# CH32V203K8T6-R0.net
KiCad netlist of a schematic drawn in Altium Designer
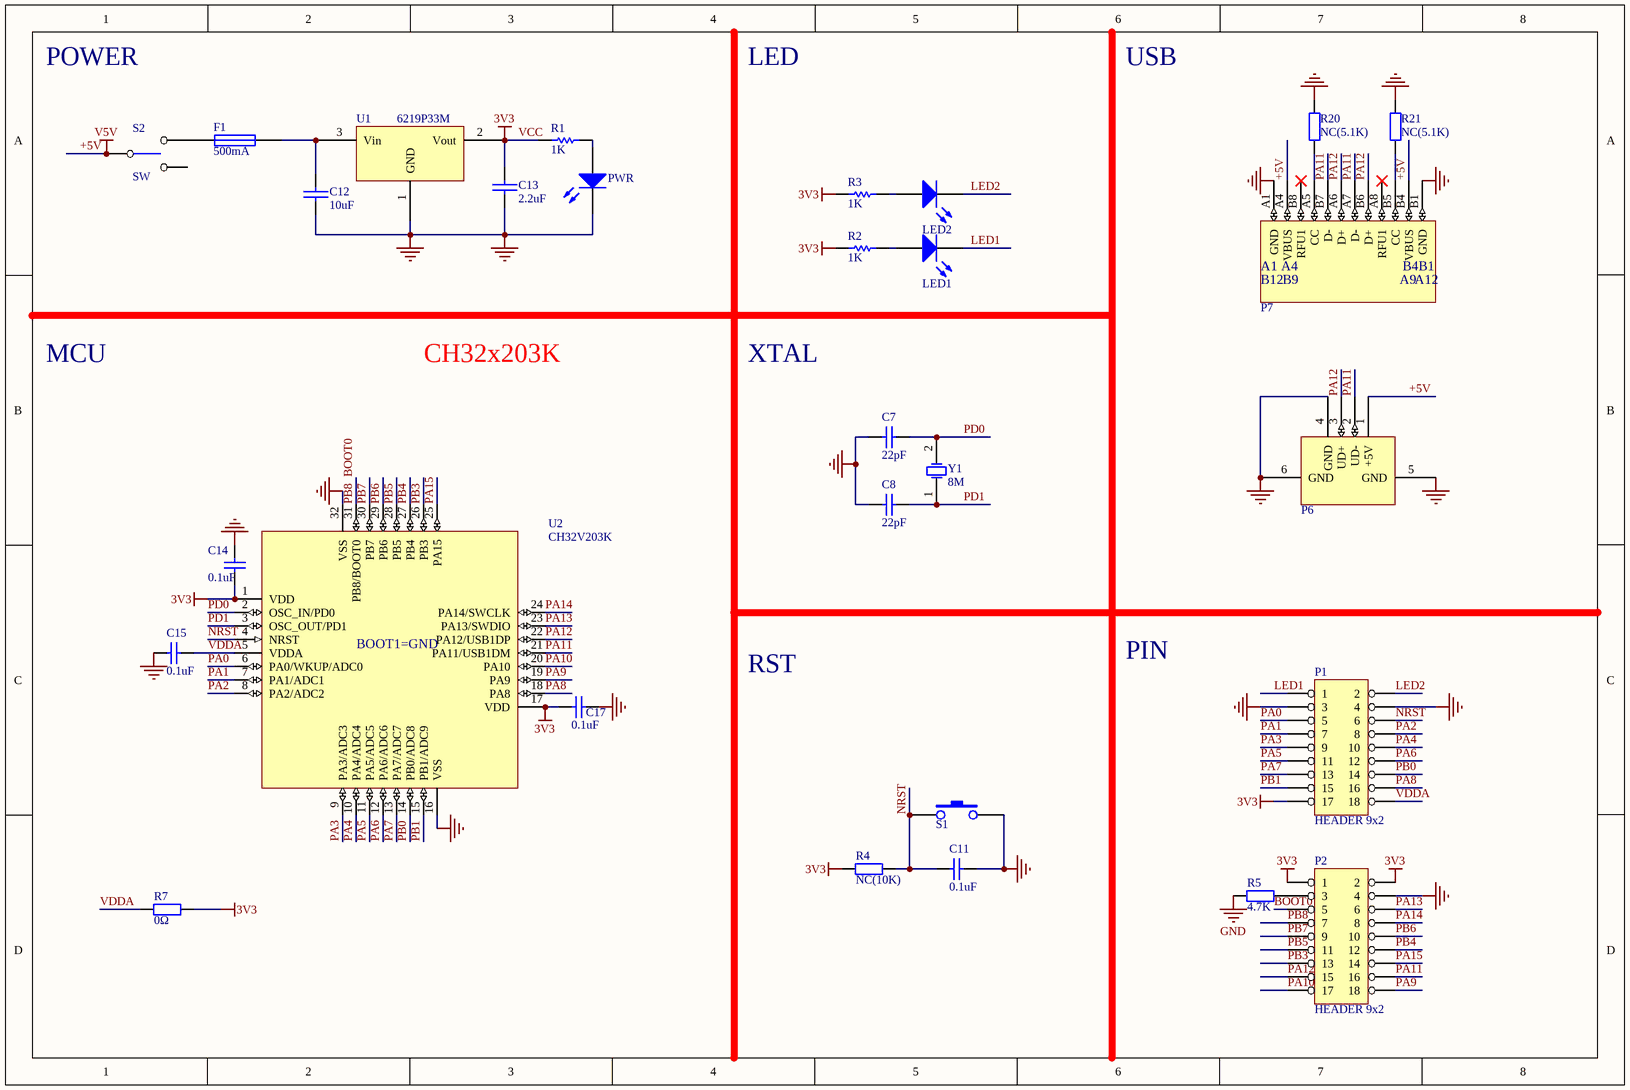
[diagram p0: CH32V203K8T6-R0.SchDoc]

(export (version "E")
  (design (tool "Eeschema 10.0.6"))
  (components
    (comp (ref "C7")
      (value "22pF")
      (footprint "0603_C")
      (description "Capacitor")
      (fields (field (name "PUBLISHER") "Altium Limited"))
      (libsource (lib "*") (part "Cap"))
    )
    (comp (ref "C8")
      (value "22pF")
      (footprint "0603_C")
      (description "Capacitor")
      (fields (field (name "PUBLISHER") "Altium Limited"))
      (libsource (lib "*") (part "Cap"))
    )
    (comp (ref "C11")
      (value "0.1uF")
      (footprint "0603_C")
      (description "Capacitor")
      (fields (field (name "PUBLISHER") "Altium Limited"))
      (libsource (lib "*") (part "Cap"))
    )
    (comp (ref "C12")
      (value "10uF")
      (footprint "3216_C")
      (description "Capacitor")
      (libsource (lib "wch_sch_others") (part "CAP"))
    )
    (comp (ref "C13")
      (value "2.2uF")
      (footprint "0603_C")
      (description "Capacitor")
      (libsource (lib "wch_sch_others") (part "CAP"))
    )
    (comp (ref "C14")
      (value "0.1uF")
      (footprint "0603_C")
      (description "Capacitor")
      (fields (field (name "PUBLISHER") "Altium Limited"))
      (libsource (lib "*") (part "Cap"))
    )
    (comp (ref "C15")
      (value "0.1uF")
      (footprint "0603_C")
      (description "Capacitor")
      (fields (field (name "PUBLISHER") "Altium Limited"))
      (libsource (lib "*") (part "Cap"))
    )
    (comp (ref "C17")
      (value "0.1uF")
      (footprint "0603_C")
      (description "Capacitor")
      (fields (field (name "PUBLISHER") "Altium Limited"))
      (libsource (lib "*") (part "Cap"))
    )
    (comp (ref "F1")
      (value "500mA")
      (footprint "0603")
      (description "Fuse")
      (libsource (lib "*") (part "FUSE1"))
    )
    (comp (ref "LED1")
      (value "LED1   blue")
      (footprint "0603+")
      (description "Typical INFRARED GaAs LED")
      (fields (field (name "PUBLISHER") "Altium Limited"))
      (libsource (lib "*") (part "LED0"))
    )
    (comp (ref "LED2")
      (value "LED2  blue")
      (footprint "0603+")
      (description "Typical INFRARED GaAs LED")
      (fields (field (name "PUBLISHER") "Altium Limited"))
      (libsource (lib "*") (part "LED0"))
    )
    (comp (ref "P1")
      (value "HEADER 9x2")
      (footprint "MYPCB:IDC18-2.54MM")
      (description "Header, 9-Pin, Dual row")
      (libsource (lib "wch_sch_others") (part "HEADER 9x2"))
    )
    (comp (ref "P2")
      (value "HEADER 9x2")
      (footprint "MYPCB:IDC18-2.54MM")
      (description "Header, 9-Pin, Dual row")
      (libsource (lib "wch_sch_others") (part "HEADER 9x2"))
    )
    (comp (ref "P6")
      (value "USB_A")
      (footprint "USBAF")
      (description "USB Port")
      (libsource (lib "*") (part "USB"))
    )
    (comp (ref "P7")
      (value "TYPE-C")
      (footprint "TYPE-C-Receptacle-2.0")
      (libsource (lib "*") (part "TYPE-C1"))
    )
    (comp (ref "PWR")
      (value "POWER  red")
      (footprint "0603+")
      (description "Typical INFRARED GaAs LED")
      (fields (field (name "PUBLISHER") "Altium Limited"))
      (libsource (lib "*") (part "LED0"))
    )
    (comp (ref "R1")
      (value "1K")
      (footprint "0603")
      (description "Semiconductor Resistor")
      (fields (field (name "PUBLISHER") "Altium Limited"))
      (libsource (lib "*") (part "Res Semi"))
    )
    (comp (ref "R2")
      (value "1K")
      (footprint "0603")
      (description "Semiconductor Resistor")
      (fields (field (name "PUBLISHER") "Altium Limited"))
      (libsource (lib "*") (part "Res Semi"))
    )
    (comp (ref "R3")
      (value "1K")
      (footprint "0603")
      (description "Semiconductor Resistor")
      (fields (field (name "PUBLISHER") "Altium Limited"))
      (libsource (lib "*") (part "Res Semi"))
    )
    (comp (ref "R4")
      (value "NC(10K)")
      (footprint "0603")
      (description "Resistor")
      (fields (field (name "PUBLISHER") "Altium Limited"))
      (libsource (lib "*") (part "Res2"))
    )
    (comp (ref "R5")
      (value "4.7K")
      (footprint "0603")
      (description "Resistor")
      (fields (field (name "PUBLISHER") "Altium Limited"))
      (libsource (lib "") (part "Res2_1"))
    )
    (comp (ref "R7")
      (value "0Ω")
      (footprint "0603")
      (description "Resistor")
      (fields (field (name "PUBLISHER") "Altium Limited"))
      (libsource (lib "*") (part "Res2"))
    )
    (comp (ref "R20")
      (value "NC(5.1K)")
      (footprint "0603")
      (description "Resistor")
      (libsource (lib "Miscellaneous Devices") (part "Res2"))
    )
    (comp (ref "R21")
      (value "NC(5.1K)")
      (footprint "0603")
      (description "Resistor")
      (libsource (lib "Miscellaneous Devices") (part "Res2"))
    )
    (comp (ref "S1") (value "RST") (footprint "SMD_6.1x3.65x2.5mm-KEY") (libsource (lib "*") (part "KEY")))
    (comp (ref "S2") (value "SW") (footprint "KEY2") (libsource (lib "*") (part "SW")))
    (comp (ref "U1")
      (value "6219P33M")
      (footprint "SOT-23")
      (libsource (lib "wch_sch_others") (part "6219P33M"))
    )
    (comp (ref "U2")
      (value "CH32V203K")
      (footprint "LQFP32")
      (description "RISC-V LMD-MCU, 144MHz, USB FS, CAN")
      (libsource (lib "CHXXX") (part "CH32V203K"))
    )
    (comp (ref "Y1")
      (value "8M")
      (footprint "XT_AT49")
      (description "Crystal Oscillator")
      (fields (field (name "PUBLISHER") "Altium Limited"))
      (libsource (lib "*") (part "XTAL"))
    )
  )
  (nets
    (net (code "2") (name "/BOOT0") (class "Default")
      (node (ref "P2") (pin "5") (pinfunction "5_5") (pintype "passive"))
      (node (ref "P2") (pin "7") (pinfunction "7_7") (pintype "passive"))
      (node (ref "U2") (pin "31") (pinfunction "PB8/BOOT0_31") (pintype "bidirectional"))
    )
    (net (code "3") (name "/LED1") (class "Default")
      (node (ref "LED1") (pin "2") (pinfunction "K_2") (pintype "passive"))
      (node (ref "P1") (pin "1") (pinfunction "1_1") (pintype "passive"))
    )
    (net (code "4") (name "/LED2") (class "Default")
      (node (ref "LED2") (pin "2") (pinfunction "K_2") (pintype "passive"))
      (node (ref "P1") (pin "2") (pinfunction "2_2") (pintype "passive"))
    )
    (net (code "5") (name "/NRST") (class "Default")
      (node (ref "C11") (pin "2") (pinfunction "2_2") (pintype "passive"))
      (node (ref "P1") (pin "6") (pinfunction "6_6") (pintype "passive"))
      (node (ref "R4") (pin "1") (pinfunction "1_1") (pintype "passive"))
      (node (ref "S1") (pin "1") (pinfunction "1_1") (pintype "passive"))
      (node (ref "U2") (pin "4") (pinfunction "NRST_4") (pintype "input"))
    )
    (net (code "6") (name "/PA0") (class "Default")
      (node (ref "P1") (pin "5") (pinfunction "5_5") (pintype "passive"))
      (node (ref "U2") (pin "6") (pinfunction "PA0/WKUP/ADC0_6") (pintype "bidirectional"))
    )
    (net (code "7") (name "/PA1") (class "Default")
      (node (ref "P1") (pin "7") (pinfunction "7_7") (pintype "passive"))
      (node (ref "U2") (pin "7") (pinfunction "PA1/ADC1_7") (pintype "bidirectional"))
    )
    (net (code "8") (name "/PA2") (class "Default")
      (node (ref "P1") (pin "8") (pinfunction "8_8") (pintype "passive"))
      (node (ref "U2") (pin "8") (pinfunction "PA2/ADC2_8") (pintype "bidirectional"))
    )
    (net (code "9") (name "/PA3") (class "Default")
      (node (ref "P1") (pin "9") (pinfunction "9_9") (pintype "passive"))
      (node (ref "U2") (pin "9") (pinfunction "PA3/ADC3_9") (pintype "bidirectional"))
    )
    (net (code "10") (name "/PA4") (class "Default")
      (node (ref "P1") (pin "10") (pinfunction "10_10") (pintype "passive"))
      (node (ref "U2") (pin "10") (pinfunction "PA4/ADC4_10") (pintype "bidirectional"))
    )
    (net (code "11") (name "/PA5") (class "Default")
      (node (ref "P1") (pin "11") (pinfunction "11_11") (pintype "passive"))
      (node (ref "U2") (pin "11") (pinfunction "PA5/ADC5_11") (pintype "bidirectional"))
    )
    (net (code "12") (name "/PA6") (class "Default")
      (node (ref "P1") (pin "12") (pinfunction "12_12") (pintype "passive"))
      (node (ref "U2") (pin "12") (pinfunction "PA6/ADC6_12") (pintype "bidirectional"))
    )
    (net (code "13") (name "/PA7") (class "Default")
      (node (ref "P1") (pin "13") (pinfunction "13_13") (pintype "passive"))
      (node (ref "U2") (pin "13") (pinfunction "PA7/ADC7_13") (pintype "bidirectional"))
    )
    (net (code "14") (name "/PA8") (class "Default")
      (node (ref "P1") (pin "16") (pinfunction "16_16") (pintype "passive"))
      (node (ref "U2") (pin "18") (pinfunction "PA8_18") (pintype "bidirectional"))
    )
    (net (code "15") (name "/PA9") (class "Default")
      (node (ref "P2") (pin "18") (pinfunction "18_18") (pintype "passive"))
      (node (ref "U2") (pin "19") (pinfunction "PA9_19") (pintype "bidirectional"))
    )
    (net (code "16") (name "/PA10") (class "Default")
      (node (ref "P2") (pin "17") (pinfunction "17_17") (pintype "passive"))
      (node (ref "U2") (pin "20") (pinfunction "PA10_20") (pintype "bidirectional"))
    )
    (net (code "17") (name "/PA11") (class "Default")
      (node (ref "P2") (pin "16") (pinfunction "16_16") (pintype "passive"))
      (node (ref "P6") (pin "2") (pinfunction "UD-_2") (pintype "bidirectional"))
      (node (ref "P7") (pin "A7") (pinfunction "D-_A7") (pintype "bidirectional"))
      (node (ref "P7") (pin "B7") (pinfunction "D-_B7") (pintype "bidirectional"))
      (node (ref "U2") (pin "21") (pinfunction "PA11/USB1DM_21") (pintype "bidirectional"))
    )
    (net (code "18") (name "/PA12") (class "Default")
      (node (ref "P2") (pin "15") (pinfunction "15_15") (pintype "passive"))
      (node (ref "P6") (pin "3") (pinfunction "UD+_3") (pintype "bidirectional"))
      (node (ref "P7") (pin "A6") (pinfunction "D+_A6") (pintype "bidirectional"))
      (node (ref "P7") (pin "B6") (pinfunction "D+_B6") (pintype "bidirectional"))
      (node (ref "U2") (pin "22") (pinfunction "PA12/USB1DP_22") (pintype "bidirectional"))
    )
    (net (code "19") (name "/PA13") (class "Default")
      (node (ref "P2") (pin "6") (pinfunction "6_6") (pintype "passive"))
      (node (ref "U2") (pin "23") (pinfunction "PA13/SWDIO_23") (pintype "bidirectional"))
    )
    (net (code "20") (name "/PA14") (class "Default")
      (node (ref "P2") (pin "8") (pinfunction "8_8") (pintype "passive"))
      (node (ref "U2") (pin "24") (pinfunction "PA14/SWCLK_24") (pintype "bidirectional"))
    )
    (net (code "21") (name "/PA15") (class "Default")
      (node (ref "P2") (pin "14") (pinfunction "14_14") (pintype "passive"))
      (node (ref "U2") (pin "25") (pinfunction "PA15_25") (pintype "bidirectional"))
    )
    (net (code "22") (name "/PB0") (class "Default")
      (node (ref "P1") (pin "14") (pinfunction "14_14") (pintype "passive"))
      (node (ref "U2") (pin "14") (pinfunction "PB0/ADC8_14") (pintype "bidirectional"))
    )
    (net (code "23") (name "/PB1") (class "Default")
      (node (ref "P1") (pin "15") (pinfunction "15_15") (pintype "passive"))
      (node (ref "U2") (pin "15") (pinfunction "PB1/ADC9_15") (pintype "bidirectional"))
    )
    (net (code "24") (name "/PB3") (class "Default")
      (node (ref "P2") (pin "13") (pinfunction "13_13") (pintype "passive"))
      (node (ref "U2") (pin "26") (pinfunction "PB3_26") (pintype "bidirectional"))
    )
    (net (code "25") (name "/PB4") (class "Default")
      (node (ref "P2") (pin "12") (pinfunction "12_12") (pintype "passive"))
      (node (ref "U2") (pin "27") (pinfunction "PB4_27") (pintype "bidirectional"))
    )
    (net (code "26") (name "/PB5") (class "Default")
      (node (ref "P2") (pin "11") (pinfunction "11_11") (pintype "passive"))
      (node (ref "U2") (pin "28") (pinfunction "PB5_28") (pintype "bidirectional"))
    )
    (net (code "27") (name "/PB6") (class "Default")
      (node (ref "P2") (pin "10") (pinfunction "10_10") (pintype "passive"))
      (node (ref "U2") (pin "29") (pinfunction "PB6_29") (pintype "bidirectional"))
    )
    (net (code "28") (name "/PB7") (class "Default")
      (node (ref "P2") (pin "9") (pinfunction "9_9") (pintype "passive"))
      (node (ref "U2") (pin "30") (pinfunction "PB7_30") (pintype "bidirectional"))
    )
    (net (code "29") (name "/PD0") (class "Default")
      (node (ref "C7") (pin "2") (pinfunction "2_2") (pintype "passive"))
      (node (ref "U2") (pin "2") (pinfunction "OSC_IN/PD0_2") (pintype "bidirectional"))
      (node (ref "Y1") (pin "2") (pinfunction "OSC2_2") (pintype "passive"))
    )
    (net (code "30") (name "/PD1") (class "Default")
      (node (ref "C8") (pin "2") (pinfunction "2_2") (pintype "passive"))
      (node (ref "U2") (pin "3") (pinfunction "OSC_OUT/PD1_3") (pintype "bidirectional"))
      (node (ref "Y1") (pin "1") (pinfunction "OSC1_1") (pintype "passive"))
    )
    (net (code "31") (name "/VDDA") (class "Default")
      (node (ref "C15") (pin "1") (pinfunction "1_1") (pintype "passive"))
      (node (ref "P1") (pin "18") (pinfunction "18_18") (pintype "passive"))
      (node (ref "R7") (pin "2") (pinfunction "2_2") (pintype "passive"))
      (node (ref "U2") (pin "5") (pinfunction "VDDA_5") (pintype "power_in"))
    )
    (net (code "32") (name "3V3") (class "Default")
      (node (ref "C13") (pin "2") (pinfunction "2_2") (pintype "passive"))
      (node (ref "C14") (pin "2") (pinfunction "2_2") (pintype "passive"))
      (node (ref "C17") (pin "1") (pinfunction "1_1") (pintype "passive"))
      (node (ref "P1") (pin "17") (pinfunction "17_17") (pintype "passive"))
      (node (ref "P2") (pin "1") (pinfunction "1_1") (pintype "passive"))
      (node (ref "P2") (pin "2") (pinfunction "2_2") (pintype "passive"))
      (node (ref "R1") (pin "2") (pinfunction "2_2") (pintype "passive"))
      (node (ref "R2") (pin "1") (pinfunction "1_1") (pintype "passive"))
      (node (ref "R3") (pin "1") (pinfunction "1_1") (pintype "passive"))
      (node (ref "R4") (pin "2") (pinfunction "2_2") (pintype "passive"))
      (node (ref "R7") (pin "1") (pinfunction "1_1") (pintype "passive"))
      (node (ref "U1") (pin "2") (pinfunction "Vout_2") (pintype "passive"))
      (node (ref "U2") (pin "1") (pinfunction "VDD_1") (pintype "power_in"))
      (node (ref "U2") (pin "17") (pinfunction "VDD_17") (pintype "power_in"))
    )
    (net (code "33") (name "GND") (class "Default")
      (node (ref "C11") (pin "1") (pinfunction "1_1") (pintype "passive"))
      (node (ref "C12") (pin "2") (pinfunction "2_2") (pintype "passive"))
      (node (ref "C13") (pin "1") (pinfunction "1_1") (pintype "passive"))
      (node (ref "C14") (pin "1") (pinfunction "1_1") (pintype "passive"))
      (node (ref "C15") (pin "2") (pinfunction "2_2") (pintype "passive"))
      (node (ref "C17") (pin "2") (pinfunction "2_2") (pintype "passive"))
      (node (ref "C7") (pin "1") (pinfunction "1_1") (pintype "passive"))
      (node (ref "C8") (pin "1") (pinfunction "1_1") (pintype "passive"))
      (node (ref "P1") (pin "3") (pinfunction "3_3") (pintype "passive"))
      (node (ref "P1") (pin "4") (pinfunction "4_4") (pintype "passive"))
      (node (ref "P2") (pin "4") (pinfunction "4_4") (pintype "passive"))
      (node (ref "P6") (pin "4") (pinfunction "GND_4") (pintype "power_in"))
      (node (ref "P6") (pin "5") (pinfunction "GND_5") (pintype "power_in"))
      (node (ref "P6") (pin "6") (pinfunction "GND_6") (pintype "power_in"))
      (node (ref "P7") (pin "A1") (pinfunction "GND_A1") (pintype "bidirectional"))
      (node (ref "P7") (pin "B1") (pinfunction "GND_B1") (pintype "bidirectional"))
      (node (ref "PWR") (pin "2") (pinfunction "K_2") (pintype "passive"))
      (node (ref "R20") (pin "2") (pinfunction "2_2") (pintype "passive"))
      (node (ref "R21") (pin "2") (pinfunction "2_2") (pintype "passive"))
      (node (ref "R5") (pin "1") (pinfunction "1_1") (pintype "passive"))
      (node (ref "S1") (pin "2") (pinfunction "2_2") (pintype "passive"))
      (node (ref "U1") (pin "1") (pinfunction "GND_1") (pintype "passive"))
      (node (ref "U2") (pin "16") (pinfunction "VSS_16") (pintype "power_in"))
      (node (ref "U2") (pin "32") (pinfunction "VSS_32") (pintype "power_in"))
    )
    (net (code "34") (name "Net-(F1-Pad1)") (class "Default")
      (node (ref "F1") (pin "1") (pinfunction "1_1") (pintype "passive"))
      (node (ref "S2") (pin "3") (pinfunction "3_3") (pintype "passive"))
    )
    (net (code "35") (name "Net-(LED1-A)") (class "Default")
      (node (ref "LED1") (pin "1") (pinfunction "A_1") (pintype "passive"))
      (node (ref "R2") (pin "2") (pinfunction "2_2") (pintype "passive"))
    )
    (net (code "36") (name "Net-(LED2-A)") (class "Default")
      (node (ref "LED2") (pin "1") (pinfunction "A_1") (pintype "passive"))
      (node (ref "R3") (pin "2") (pinfunction "2_2") (pintype "passive"))
    )
    (net (code "37") (name "Net-(P2-Pad3)") (class "Default")
      (node (ref "P2") (pin "3") (pinfunction "3_3") (pintype "passive"))
      (node (ref "R5") (pin "2") (pinfunction "2_2") (pintype "passive"))
    )
    (net (code "38") (name "Net-(P7-CC-PadA5)") (class "Default")
      (node (ref "P7") (pin "A5") (pinfunction "CC_A5") (pintype "bidirectional"))
      (node (ref "R20") (pin "1") (pinfunction "1_1") (pintype "passive"))
    )
    (net (code "39") (name "Net-(P7-CC-PadB5)") (class "Default")
      (node (ref "P7") (pin "B5") (pinfunction "CC_B5") (pintype "bidirectional"))
      (node (ref "R21") (pin "1") (pinfunction "1_1") (pintype "passive"))
    )
    (net (code "40") (name "Net-(PWR-A)") (class "Default")
      (node (ref "PWR") (pin "1") (pinfunction "A_1") (pintype "passive"))
      (node (ref "R1") (pin "1") (pinfunction "1_1") (pintype "passive"))
    )
    (net (code "41") (name "Net-(U1-Vin)") (class "Default")
      (node (ref "C12") (pin "1") (pinfunction "1_1") (pintype "passive"))
      (node (ref "F1") (pin "2") (pinfunction "2_2") (pintype "passive"))
      (node (ref "U1") (pin "3") (pinfunction "Vin_3") (pintype "passive"))
    )
    (net (code "42") (name "V5V") (class "Default")
      (node (ref "P6") (pin "1") (pinfunction "+5V_1") (pintype "power_in"))
      (node (ref "P7") (pin "A4") (pinfunction "VBUS_A4") (pintype "bidirectional"))
      (node (ref "P7") (pin "B4") (pinfunction "VBUS_B4") (pintype "bidirectional"))
      (node (ref "S2") (pin "1") (pinfunction "1_1") (pintype "passive"))
    )
    (net (code "43") (name "unconnected-(P7-RFU1-PadA8)") (class "Default")
      (node (ref "P7") (pin "A8") (pinfunction "RFU1_A8") (pintype "bidirectional+no_connect"))
    )
    (net (code "44") (name "unconnected-(P7-RFU1-PadB8)") (class "Default")
      (node (ref "P7") (pin "B8") (pinfunction "RFU1_B8") (pintype "bidirectional+no_connect"))
    )
    (net (code "45") (name "unconnected-(S2-Pad2)") (class "Default")
      (node (ref "S2") (pin "2") (pinfunction "2_2") (pintype "passive"))
    )
  )
)
